# PCB_3U_DDS.net
KiCad netlist of a schematic drawn in Altium Designer
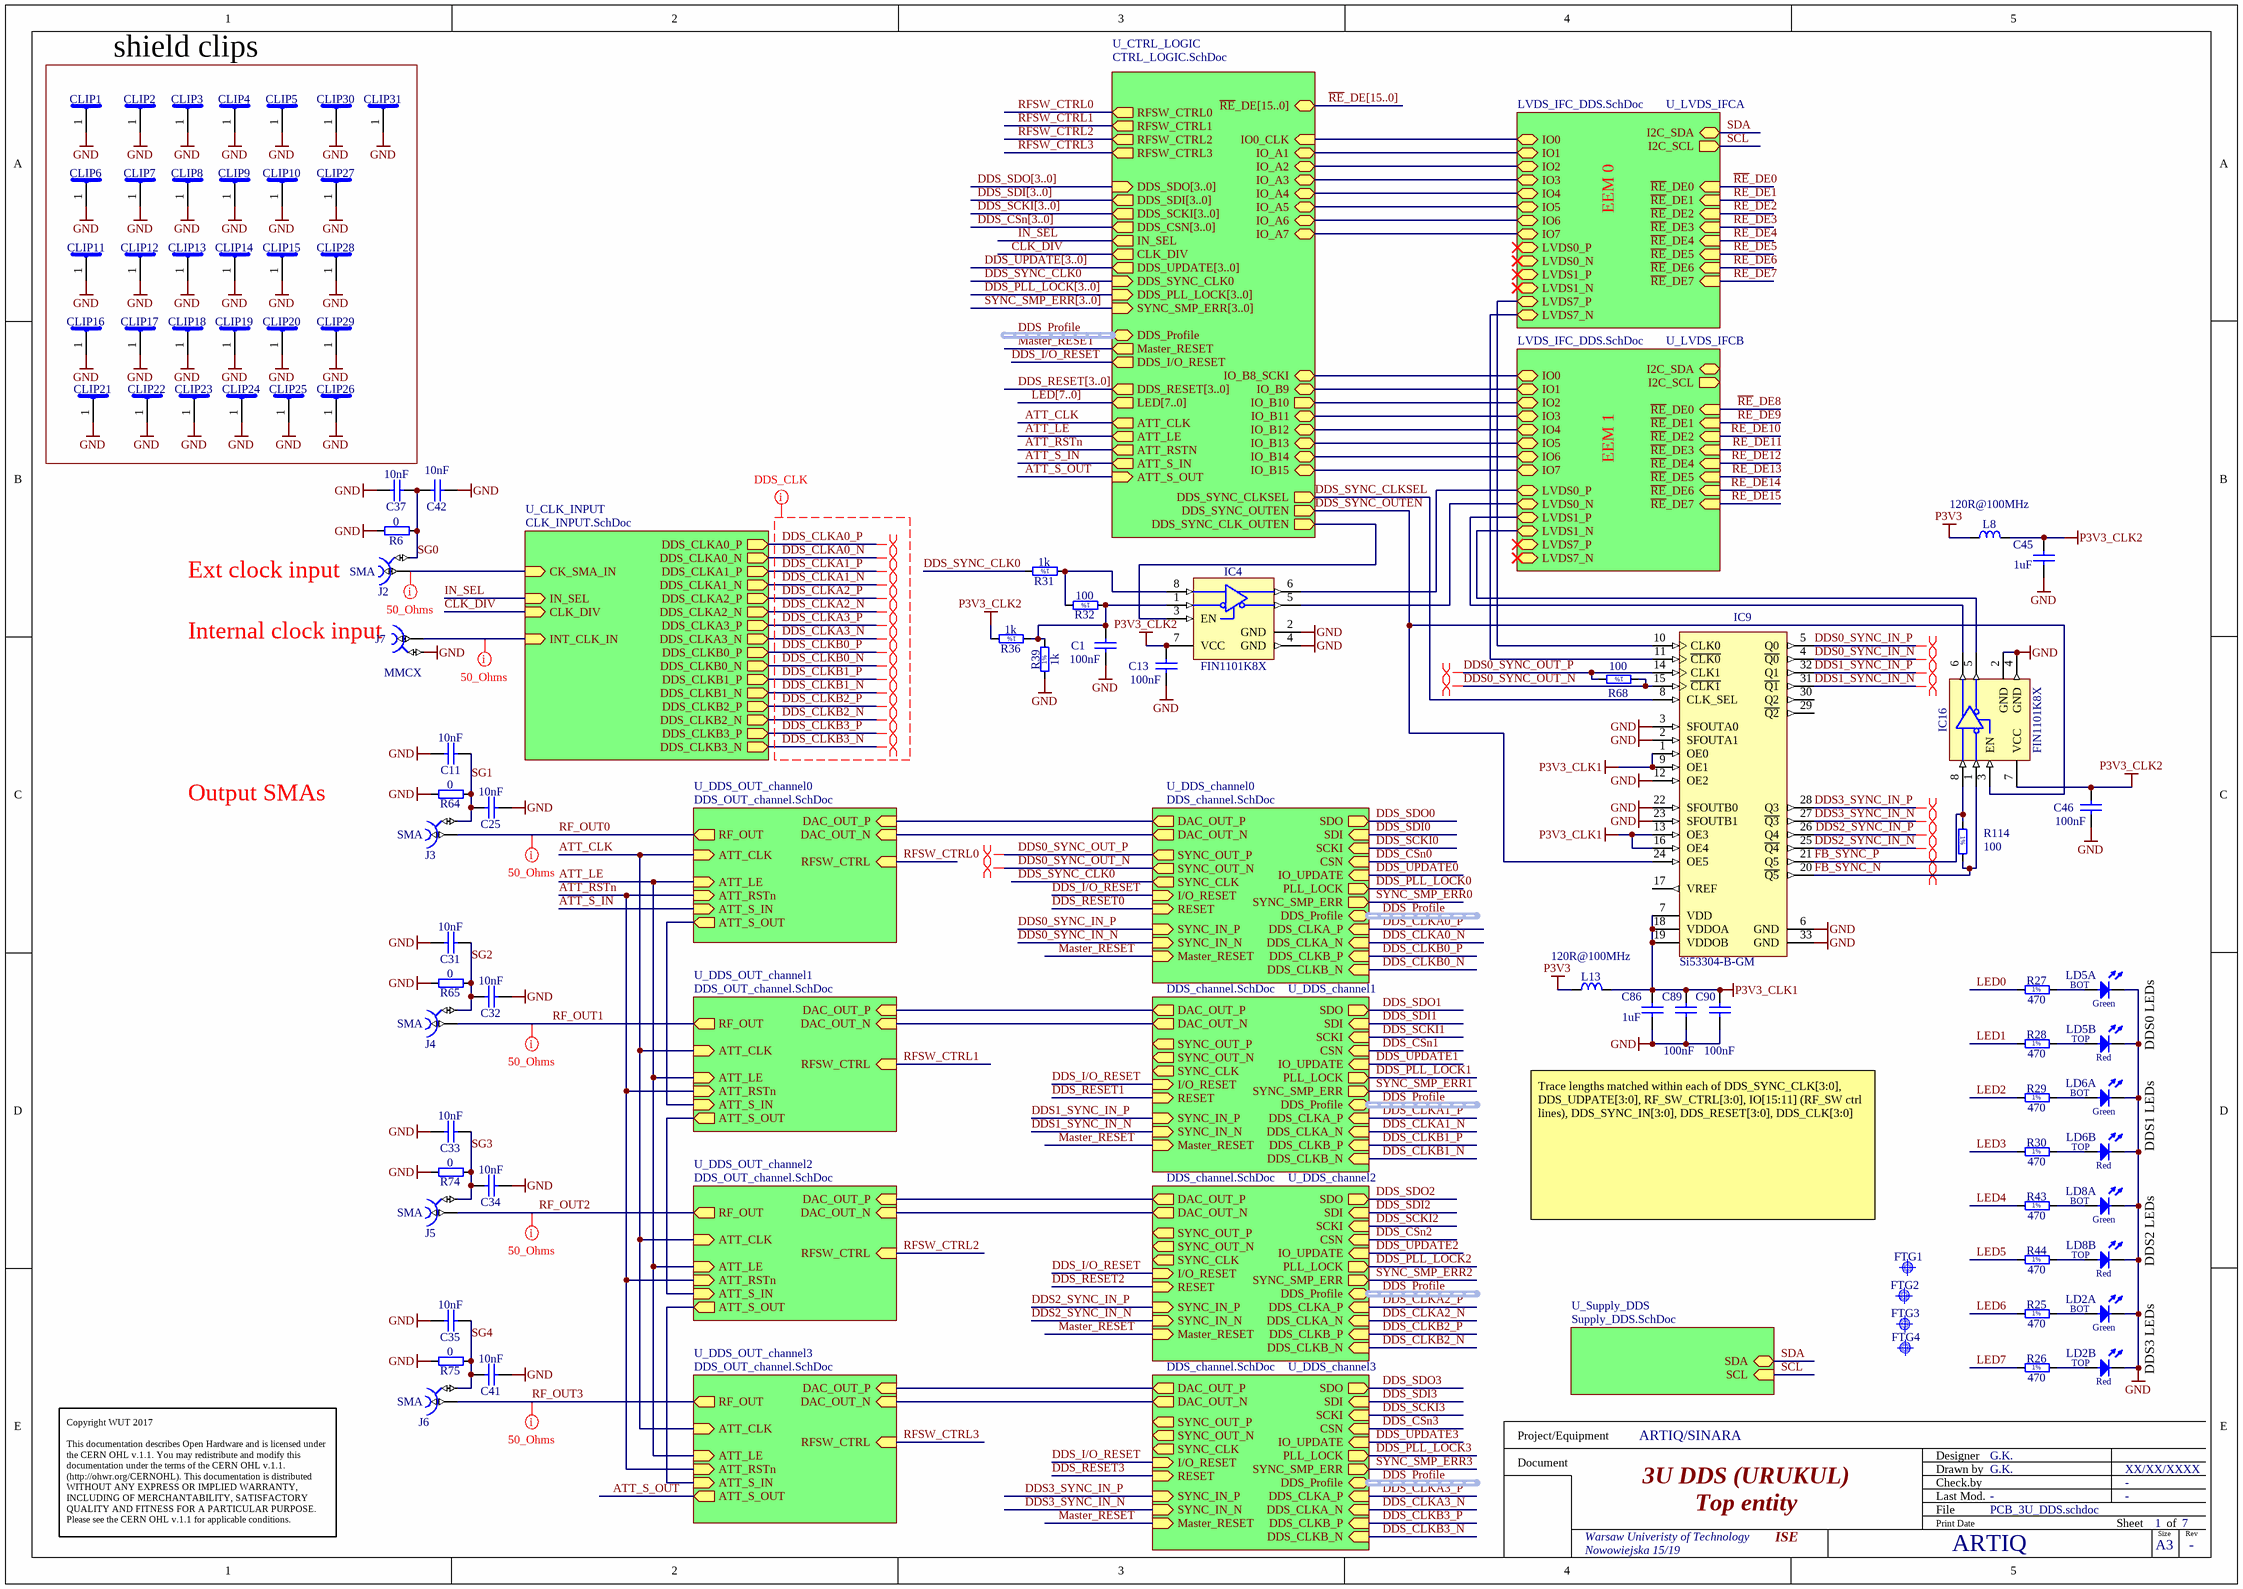
[diagram p0: PCB_3U_DDS.schdoc]

(export (version "E")
  (design (tool "Eeschema 10.0.6"))
  (components
    (comp (ref "C1")
      (value "100nF")
      (footprint "CAPC1005X55N")
      (description "Non-polarised capacitor")
      (fields
        (field (name "PART NUMBER") "CC0402_100NF_16V_10%_X5R")
        (field (name "VOLTAGE") "16V")
        (field (name "AUTHOR") "CERN DEM JLC")
      )
      (libsource (lib "Capacitors") (part "Capacitor - non polarized"))
    )
    (comp (ref "C11")
      (value "10nF")
      (footprint "CAPC1005X55N")
      (description "Non-polarised capacitor")
      (fields
        (field (name "PART NUMBER") "CC0402_10NF_16V_10%_X7R")
        (field (name "VOLTAGE") "16V")
        (field (name "AUTHOR") "CERN DEM JLC")
      )
      (libsource (lib "Capacitors") (part "Capacitor - non polarized"))
    )
    (comp (ref "C13")
      (value "100nF")
      (footprint "CAPC1005X55N")
      (description "Non-polarised capacitor")
      (fields
        (field (name "PART NUMBER") "CC0402_100NF_16V_10%_X5R")
        (field (name "VOLTAGE") "16V")
        (field (name "AUTHOR") "CERN DEM JLC")
      )
      (libsource (lib "Capacitors") (part "Capacitor - non polarized"))
    )
    (comp (ref "C25")
      (value "10nF")
      (footprint "CAPC1005X55N")
      (description "Non-polarised capacitor")
      (fields
        (field (name "PART NUMBER") "CC0402_10NF_16V_10%_X7R")
        (field (name "VOLTAGE") "16V")
        (field (name "AUTHOR") "CERN DEM JLC")
      )
      (libsource (lib "Capacitors") (part "Capacitor - non polarized"))
    )
    (comp (ref "C31")
      (value "10nF")
      (footprint "CAPC1005X55N")
      (description "Non-polarised capacitor")
      (fields
        (field (name "PART NUMBER") "CC0402_10NF_16V_10%_X7R")
        (field (name "VOLTAGE") "16V")
        (field (name "AUTHOR") "CERN DEM JLC")
      )
      (libsource (lib "Capacitors") (part "Capacitor - non polarized"))
    )
    (comp (ref "C32")
      (value "10nF")
      (footprint "CAPC1005X55N")
      (description "Non-polarised capacitor")
      (fields
        (field (name "PART NUMBER") "CC0402_10NF_16V_10%_X7R")
        (field (name "VOLTAGE") "16V")
        (field (name "AUTHOR") "CERN DEM JLC")
      )
      (libsource (lib "Capacitors") (part "Capacitor - non polarized"))
    )
    (comp (ref "C33")
      (value "10nF")
      (footprint "CAPC1005X55N")
      (description "Non-polarised capacitor")
      (fields
        (field (name "PART NUMBER") "CC0402_10NF_16V_10%_X7R")
        (field (name "VOLTAGE") "16V")
        (field (name "AUTHOR") "CERN DEM JLC")
      )
      (libsource (lib "Capacitors") (part "Capacitor - non polarized"))
    )
    (comp (ref "C34")
      (value "10nF")
      (footprint "CAPC1005X55N")
      (description "Non-polarised capacitor")
      (fields
        (field (name "PART NUMBER") "CC0402_10NF_16V_10%_X7R")
        (field (name "VOLTAGE") "16V")
        (field (name "AUTHOR") "CERN DEM JLC")
      )
      (libsource (lib "Capacitors") (part "Capacitor - non polarized"))
    )
    (comp (ref "C35")
      (value "10nF")
      (footprint "CAPC1005X55N")
      (description "Non-polarised capacitor")
      (fields
        (field (name "PART NUMBER") "CC0402_10NF_16V_10%_X7R")
        (field (name "VOLTAGE") "16V")
        (field (name "AUTHOR") "CERN DEM JLC")
      )
      (libsource (lib "Capacitors") (part "Capacitor - non polarized"))
    )
    (comp (ref "C37")
      (value "10nF")
      (footprint "CAPC1005X55N")
      (description "Non-polarised capacitor")
      (fields
        (field (name "PART NUMBER") "CC0402_10NF_16V_10%_X7R")
        (field (name "VOLTAGE") "16V")
        (field (name "AUTHOR") "CERN DEM JLC")
      )
      (libsource (lib "Capacitors") (part "Capacitor - non polarized"))
    )
    (comp (ref "C41")
      (value "10nF")
      (footprint "CAPC1005X55N")
      (description "Non-polarised capacitor")
      (fields
        (field (name "PART NUMBER") "CC0402_10NF_16V_10%_X7R")
        (field (name "VOLTAGE") "16V")
        (field (name "AUTHOR") "CERN DEM JLC")
      )
      (libsource (lib "Capacitors") (part "Capacitor - non polarized"))
    )
    (comp (ref "C42")
      (value "10nF")
      (footprint "CAPC1005X55N")
      (description "Non-polarised capacitor")
      (fields
        (field (name "PART NUMBER") "CC0402_10NF_16V_10%_X7R")
        (field (name "VOLTAGE") "16V")
        (field (name "AUTHOR") "CERN DEM JLC")
      )
      (libsource (lib "Capacitors") (part "Capacitor - non polarized"))
    )
    (comp (ref "C45")
      (value "1uF")
      (footprint "CAPC1005X55N")
      (description "Non-polarised capacitor")
      (fields
        (field (name "PART NUMBER") "CC0402_1UF_16V_10%_X5R")
        (field (name "VOLTAGE") "16V")
        (field (name "AUTHOR") "CERN DEM JLC")
      )
      (libsource (lib "Capacitors") (part "Capacitor - non polarized"))
    )
    (comp (ref "C46")
      (value "100nF")
      (footprint "CAPC1005X55N")
      (description "Non-polarised capacitor")
      (fields
        (field (name "PART NUMBER") "CC0402_100NF_16V_10%_X5R")
        (field (name "VOLTAGE") "16V")
        (field (name "AUTHOR") "CERN DEM JLC")
      )
      (libsource (lib "Capacitors") (part "Capacitor - non polarized"))
    )
    (comp (ref "C86")
      (value "1uF")
      (footprint "CAPC1005X55N")
      (description "Non-polarised capacitor")
      (fields
        (field (name "PART NUMBER") "CC0402_1UF_16V_10%_X5R")
        (field (name "VOLTAGE") "16V")
        (field (name "AUTHOR") "CERN DEM JLC")
      )
      (libsource (lib "Capacitors") (part "Capacitor - non polarized"))
    )
    (comp (ref "C89")
      (value "100nF")
      (footprint "CAPC1005X55N")
      (description "Non-polarised capacitor")
      (fields
        (field (name "PART NUMBER") "CC0402_100NF_16V_10%_X5R")
        (field (name "VOLTAGE") "16V")
        (field (name "AUTHOR") "CERN DEM JLC")
      )
      (libsource (lib "Capacitors") (part "Capacitor - non polarized"))
    )
    (comp (ref "C90")
      (value "100nF")
      (footprint "CAPC1005X55N")
      (description "Non-polarised capacitor")
      (fields
        (field (name "PART NUMBER") "CC0402_100NF_16V_10%_X5R")
        (field (name "VOLTAGE") "16V")
        (field (name "AUTHOR") "CERN DEM JLC")
      )
      (libsource (lib "Capacitors") (part "Capacitor - non polarized"))
    )
    (comp (ref "CLIP1")
      (value "S1411-46R")
      (footprint "CLIP_HOLLAND-SHIELDING_LC")
      (description "Surface Mount Clip for PCB Screening Covers")
      (fields (field (name "MANUFACTURER") "HARWIN") (field (name "AUTHOR") "CERN DEM JLC"))
      (libsource (lib "LIBRARY_SCH") (part "SHIELD_CLIP"))
    )
    (comp (ref "CLIP2")
      (value "S1411-46R")
      (footprint "CLIP_HOLLAND-SHIELDING_LC")
      (description "Surface Mount Clip for PCB Screening Covers")
      (fields (field (name "MANUFACTURER") "HARWIN") (field (name "AUTHOR") "CERN DEM JLC"))
      (libsource (lib "LIBRARY_SCH") (part "SHIELD_CLIP"))
    )
    (comp (ref "CLIP3")
      (value "S1411-46R")
      (footprint "CLIP_HOLLAND-SHIELDING_LC")
      (description "Surface Mount Clip for PCB Screening Covers")
      (fields (field (name "MANUFACTURER") "HARWIN") (field (name "AUTHOR") "CERN DEM JLC"))
      (libsource (lib "LIBRARY_SCH") (part "SHIELD_CLIP"))
    )
    (comp (ref "CLIP4")
      (value "S1411-46R")
      (footprint "CLIP_HOLLAND-SHIELDING_LC")
      (description "Surface Mount Clip for PCB Screening Covers")
      (fields (field (name "MANUFACTURER") "HARWIN") (field (name "AUTHOR") "CERN DEM JLC"))
      (libsource (lib "LIBRARY_SCH") (part "SHIELD_CLIP"))
    )
    (comp (ref "CLIP5")
      (value "S1411-46R")
      (footprint "CLIP_HOLLAND-SHIELDING_LC")
      (description "Surface Mount Clip for PCB Screening Covers")
      (fields (field (name "MANUFACTURER") "HARWIN") (field (name "AUTHOR") "CERN DEM JLC"))
      (libsource (lib "LIBRARY_SCH") (part "SHIELD_CLIP"))
    )
    (comp (ref "CLIP6")
      (value "S1411-46R")
      (footprint "CLIP_HOLLAND-SHIELDING_LC")
      (description "Surface Mount Clip for PCB Screening Covers")
      (fields (field (name "MANUFACTURER") "HARWIN") (field (name "AUTHOR") "CERN DEM JLC"))
      (libsource (lib "LIBRARY_SCH") (part "SHIELD_CLIP"))
    )
    (comp (ref "CLIP7")
      (value "S1411-46R")
      (footprint "CLIP_HOLLAND-SHIELDING_LC")
      (description "Surface Mount Clip for PCB Screening Covers")
      (fields (field (name "MANUFACTURER") "HARWIN") (field (name "AUTHOR") "CERN DEM JLC"))
      (libsource (lib "LIBRARY_SCH") (part "SHIELD_CLIP"))
    )
    (comp (ref "CLIP8")
      (value "S1411-46R")
      (footprint "CLIP_HOLLAND-SHIELDING_LC")
      (description "Surface Mount Clip for PCB Screening Covers")
      (fields (field (name "MANUFACTURER") "HARWIN") (field (name "AUTHOR") "CERN DEM JLC"))
      (libsource (lib "LIBRARY_SCH") (part "SHIELD_CLIP"))
    )
    (comp (ref "CLIP9")
      (value "S1411-46R")
      (footprint "CLIP_HOLLAND-SHIELDING_LC")
      (description "Surface Mount Clip for PCB Screening Covers")
      (fields (field (name "MANUFACTURER") "HARWIN") (field (name "AUTHOR") "CERN DEM JLC"))
      (libsource (lib "LIBRARY_SCH") (part "SHIELD_CLIP"))
    )
    (comp (ref "CLIP10")
      (value "S1411-46R")
      (footprint "CLIP_HOLLAND-SHIELDING_LC")
      (description "Surface Mount Clip for PCB Screening Covers")
      (fields (field (name "MANUFACTURER") "HARWIN") (field (name "AUTHOR") "CERN DEM JLC"))
      (libsource (lib "LIBRARY_SCH") (part "SHIELD_CLIP"))
    )
    (comp (ref "CLIP11")
      (value "S1411-46R")
      (footprint "CLIP_HOLLAND-SHIELDING_LC")
      (description "Surface Mount Clip for PCB Screening Covers")
      (fields (field (name "MANUFACTURER") "HARWIN") (field (name "AUTHOR") "CERN DEM JLC"))
      (libsource (lib "LIBRARY_SCH") (part "SHIELD_CLIP"))
    )
    (comp (ref "CLIP12")
      (value "S1411-46R")
      (footprint "CLIP_HOLLAND-SHIELDING_LC")
      (description "Surface Mount Clip for PCB Screening Covers")
      (fields (field (name "MANUFACTURER") "HARWIN") (field (name "AUTHOR") "CERN DEM JLC"))
      (libsource (lib "LIBRARY_SCH") (part "SHIELD_CLIP"))
    )
    (comp (ref "CLIP13")
      (value "S1411-46R")
      (footprint "CLIP_HOLLAND-SHIELDING_LC")
      (description "Surface Mount Clip for PCB Screening Covers")
      (fields (field (name "MANUFACTURER") "HARWIN") (field (name "AUTHOR") "CERN DEM JLC"))
      (libsource (lib "LIBRARY_SCH") (part "SHIELD_CLIP"))
    )
    (comp (ref "CLIP14")
      (value "S1411-46R")
      (footprint "CLIP_HOLLAND-SHIELDING_LC")
      (description "Surface Mount Clip for PCB Screening Covers")
      (fields (field (name "MANUFACTURER") "HARWIN") (field (name "AUTHOR") "CERN DEM JLC"))
      (libsource (lib "LIBRARY_SCH") (part "SHIELD_CLIP"))
    )
    (comp (ref "CLIP15")
      (value "S1411-46R")
      (footprint "CLIP_HOLLAND-SHIELDING_LC")
      (description "Surface Mount Clip for PCB Screening Covers")
      (fields (field (name "MANUFACTURER") "HARWIN") (field (name "AUTHOR") "CERN DEM JLC"))
      (libsource (lib "LIBRARY_SCH") (part "SHIELD_CLIP"))
    )
    (comp (ref "CLIP16")
      (value "S1411-46R")
      (footprint "CLIP_HOLLAND-SHIELDING_LC")
      (description "Surface Mount Clip for PCB Screening Covers")
      (fields (field (name "MANUFACTURER") "HARWIN") (field (name "AUTHOR") "CERN DEM JLC"))
      (libsource (lib "LIBRARY_SCH") (part "SHIELD_CLIP"))
    )
    (comp (ref "CLIP17")
      (value "S1411-46R")
      (footprint "CLIP_HOLLAND-SHIELDING_LC")
      (description "Surface Mount Clip for PCB Screening Covers")
      (fields (field (name "MANUFACTURER") "HARWIN") (field (name "AUTHOR") "CERN DEM JLC"))
      (libsource (lib "LIBRARY_SCH") (part "SHIELD_CLIP"))
    )
    (comp (ref "CLIP18")
      (value "S1411-46R")
      (footprint "CLIP_HOLLAND-SHIELDING_LC")
      (description "Surface Mount Clip for PCB Screening Covers")
      (fields (field (name "MANUFACTURER") "HARWIN") (field (name "AUTHOR") "CERN DEM JLC"))
      (libsource (lib "LIBRARY_SCH") (part "SHIELD_CLIP"))
    )
    (comp (ref "CLIP19")
      (value "S1411-46R")
      (footprint "CLIP_HOLLAND-SHIELDING_LC")
      (description "Surface Mount Clip for PCB Screening Covers")
      (fields (field (name "MANUFACTURER") "HARWIN") (field (name "AUTHOR") "CERN DEM JLC"))
      (libsource (lib "LIBRARY_SCH") (part "SHIELD_CLIP"))
    )
    (comp (ref "CLIP20")
      (value "S1411-46R")
      (footprint "CLIP_HOLLAND-SHIELDING_LC")
      (description "Surface Mount Clip for PCB Screening Covers")
      (fields (field (name "MANUFACTURER") "HARWIN") (field (name "AUTHOR") "CERN DEM JLC"))
      (libsource (lib "LIBRARY_SCH") (part "SHIELD_CLIP"))
    )
    (comp (ref "CLIP21")
      (value "S1411-46R")
      (footprint "CLIP_HOLLAND-SHIELDING_LC")
      (description "Surface Mount Clip for PCB Screening Covers")
      (fields (field (name "MANUFACTURER") "HARWIN") (field (name "AUTHOR") "CERN DEM JLC"))
      (libsource (lib "LIBRARY_SCH") (part "SHIELD_CLIP"))
    )
    (comp (ref "CLIP22")
      (value "S1411-46R")
      (footprint "CLIP_HOLLAND-SHIELDING_LC")
      (description "Surface Mount Clip for PCB Screening Covers")
      (fields (field (name "MANUFACTURER") "HARWIN") (field (name "AUTHOR") "CERN DEM JLC"))
      (libsource (lib "LIBRARY_SCH") (part "SHIELD_CLIP"))
    )
    (comp (ref "CLIP23")
      (value "S1411-46R")
      (footprint "CLIP_HOLLAND-SHIELDING_LC")
      (description "Surface Mount Clip for PCB Screening Covers")
      (fields (field (name "MANUFACTURER") "HARWIN") (field (name "AUTHOR") "CERN DEM JLC"))
      (libsource (lib "LIBRARY_SCH") (part "SHIELD_CLIP"))
    )
    (comp (ref "CLIP24")
      (value "S1411-46R")
      (footprint "CLIP_HOLLAND-SHIELDING_LC")
      (description "Surface Mount Clip for PCB Screening Covers")
      (fields (field (name "MANUFACTURER") "HARWIN") (field (name "AUTHOR") "CERN DEM JLC"))
      (libsource (lib "LIBRARY_SCH") (part "SHIELD_CLIP"))
    )
    (comp (ref "CLIP25")
      (value "S1411-46R")
      (footprint "CLIP_HOLLAND-SHIELDING_LC")
      (description "Surface Mount Clip for PCB Screening Covers")
      (fields (field (name "MANUFACTURER") "HARWIN") (field (name "AUTHOR") "CERN DEM JLC"))
      (libsource (lib "LIBRARY_SCH") (part "SHIELD_CLIP"))
    )
    (comp (ref "CLIP26")
      (value "S1411-46R")
      (footprint "CLIP_HOLLAND-SHIELDING_LC")
      (description "Surface Mount Clip for PCB Screening Covers")
      (fields (field (name "MANUFACTURER") "HARWIN") (field (name "AUTHOR") "CERN DEM JLC"))
      (libsource (lib "LIBRARY_SCH") (part "SHIELD_CLIP"))
    )
    (comp (ref "CLIP27")
      (value "S1411-46R")
      (footprint "CLIP_HOLLAND-SHIELDING_LC")
      (description "Surface Mount Clip for PCB Screening Covers")
      (fields (field (name "MANUFACTURER") "HARWIN") (field (name "AUTHOR") "CERN DEM JLC"))
      (libsource (lib "LIBRARY_SCH") (part "SHIELD_CLIP"))
    )
    (comp (ref "CLIP28")
      (value "S1411-46R")
      (footprint "CLIP_HOLLAND-SHIELDING_LC")
      (description "Surface Mount Clip for PCB Screening Covers")
      (fields (field (name "MANUFACTURER") "HARWIN") (field (name "AUTHOR") "CERN DEM JLC"))
      (libsource (lib "LIBRARY_SCH") (part "SHIELD_CLIP"))
    )
    (comp (ref "CLIP29")
      (value "S1411-46R")
      (footprint "CLIP_HOLLAND-SHIELDING_LC")
      (description "Surface Mount Clip for PCB Screening Covers")
      (fields (field (name "MANUFACTURER") "HARWIN") (field (name "AUTHOR") "CERN DEM JLC"))
      (libsource (lib "LIBRARY_SCH") (part "SHIELD_CLIP"))
    )
    (comp (ref "CLIP30")
      (value "S1411-46R")
      (footprint "CLIP_HOLLAND-SHIELDING_LC")
      (description "Surface Mount Clip for PCB Screening Covers")
      (fields (field (name "MANUFACTURER") "HARWIN") (field (name "AUTHOR") "CERN DEM JLC"))
      (libsource (lib "LIBRARY_SCH") (part "SHIELD_CLIP"))
    )
    (comp (ref "CLIP31")
      (value "S1411-46R")
      (footprint "CLIP_HOLLAND-SHIELDING_LC")
      (description "Surface Mount Clip for PCB Screening Covers")
      (fields (field (name "MANUFACTURER") "HARWIN") (field (name "AUTHOR") "CERN DEM JLC"))
      (libsource (lib "LIBRARY_SCH") (part "SHIELD_CLIP"))
    )
    (comp (ref "FTG1")
      (value "Use only in PCB")
      (footprint "FIDUCIAL_TOP_C100-200")
      (description "Fiducial Target")
      (fields (field (name "PART NUMBER") "FIDUCIAL_TARGET_C100-200") (field (name "AUTHOR") "CERN DEM JLC"))
      (libsource (lib "Eletro-mechanical") (part "Fiducial Target"))
    )
    (comp (ref "FTG2")
      (value "Use only in PCB")
      (footprint "FIDUCIAL_TOP_S100-200")
      (description "Fiducial Target")
      (fields (field (name "PART NUMBER") "FIDUCIAL_TARGET_S100-200") (field (name "AUTHOR") "CERN DEM JLC"))
      (libsource (lib "Eletro-mechanical") (part "Fiducial Target"))
    )
    (comp (ref "FTG3")
      (value "Use only in PCB")
      (footprint "FIDUCIAL_TOP_S200-400")
      (description "Fiducial Target")
      (fields (field (name "PART NUMBER") "FIDUCIAL_TARGET_S200-400") (field (name "AUTHOR") "CERN DEM JLC"))
      (libsource (lib "Eletro-mechanical") (part "Fiducial Target"))
    )
    (comp (ref "FTG4")
      (value "Use only in PCB")
      (footprint "FIDUCIAL_TOP_S100-200")
      (description "Fiducial Target")
      (fields (field (name "PART NUMBER") "FIDUCIAL_TARGET_S100-200") (field (name "AUTHOR") "CERN DEM JLC"))
      (libsource (lib "Eletro-mechanical") (part "Fiducial Target"))
    )
    (comp (ref "IC4")
      (value "FIN1101K8X")
      (footprint "SOP50P310X90-8N")
      (description "LVDS Single Port High Speed Repeater")
      (fields (field (name "MANUFACTURER") "FAIRCHILD SEMICONDUCTOR") (field (name "AUTHOR") "CERN DEM JLC"))
      (libsource (lib "") (part "FIN1101K8X_1"))
    )
    (comp (ref "IC9")
      (value "Si53304-B-GM")
      (footprint "SLAB-QFN-32-2150x2150TP_M")
      (fields (field (name "MANUFACTURER") "Silicon Labs"))
      (libsource (lib "Altium Content Vault") (part "SLAB-Si533X4-QFN-32-33"))
    )
    (comp (ref "IC16")
      (value "FIN1101K8X")
      (footprint "SOP50P310X90-8N")
      (description "LVDS Single Port High Speed Repeater")
      (fields (field (name "MANUFACTURER") "FAIRCHILD SEMICONDUCTOR") (field (name "AUTHOR") "CERN DEM JLC"))
      (libsource (lib "ICs And Semiconductors") (part "FIN1101K8X"))
    )
    (comp (ref "J2")
      (value "SMA")
      (footprint "RF249BT0050GHDW")
      (description "50 Ohm Through Hole SMA Right Angle PCB Jack")
      (fields
        (field (name "PART NUMBER") "AdamTech_RF249BT0050GHDW")
        (field (name "MANUFACTURER") "AdamTech")
        (field (name "AUTHOR") "GK")
      )
      (libsource (lib "LIBRARY_SCH") (part "CON_SMA_RF249BT0050GHDW"))
    )
    (comp (ref "J3")
      (value "SMA")
      (footprint "RF249BT0050GHDW")
      (description "50 Ohm Through Hole SMA Right Angle PCB Jack")
      (fields
        (field (name "PART NUMBER") "AdamTech_RF249BT0050GHDW")
        (field (name "MANUFACTURER") "AdamTech")
        (field (name "AUTHOR") "GK")
      )
      (libsource (lib "LIBRARY_SCH") (part "CON_SMA_RF249BT0050GHDW"))
    )
    (comp (ref "J4")
      (value "SMA")
      (footprint "RF249BT0050GHDW")
      (description "50 Ohm Through Hole SMA Right Angle PCB Jack")
      (fields
        (field (name "PART NUMBER") "AdamTech_RF249BT0050GHDW")
        (field (name "MANUFACTURER") "AdamTech")
        (field (name "AUTHOR") "GK")
      )
      (libsource (lib "LIBRARY_SCH") (part "CON_SMA_RF249BT0050GHDW"))
    )
    (comp (ref "J5")
      (value "SMA")
      (footprint "RF249BT0050GHDW")
      (description "50 Ohm Through Hole SMA Right Angle PCB Jack")
      (fields
        (field (name "PART NUMBER") "AdamTech_RF249BT0050GHDW")
        (field (name "MANUFACTURER") "AdamTech")
        (field (name "AUTHOR") "GK")
      )
      (libsource (lib "LIBRARY_SCH") (part "CON_SMA_RF249BT0050GHDW"))
    )
    (comp (ref "J6")
      (value "SMA")
      (footprint "RF249BT0050GHDW")
      (description "50 Ohm Through Hole SMA Right Angle PCB Jack")
      (fields
        (field (name "PART NUMBER") "AdamTech_RF249BT0050GHDW")
        (field (name "MANUFACTURER") "AdamTech")
        (field (name "AUTHOR") "GK")
      )
      (libsource (lib "LIBRARY_SCH") (part "CON_SMA_RF249BT0050GHDW"))
    )
    (comp (ref "J7")
      (value "MMCX")
      (footprint "SAMTEC_MMCX-J-P-H-ST-TH1")
      (fields
        (field (name "PART NUMBER") "SAMTEC_MMCX-J-P-H-ST-TH1")
        (field (name "MANUFACTURER") "SAMTEC")
        (field (name "MANUFACTURER PART NUMBER") "MMCX-J-P-H-ST-TH1")
        (field (name "AUTHOR") "CERN DEM JLC")
      )
      (libsource (lib "Connectors") (part "Coax_1Female_1Shield"))
    )
    (comp (ref "L8")
      (value "120R@100MHz")
      (footprint "INDC1608X95N")
      (description "Inductor")
      (fields
        (field (name "PART NUMBER") "IND0603_MURATA_BLM18PG121SN1D")
        (field (name "POWER") "2A")
        (field (name "AUTHOR") "CERN DEM BC")
      )
      (libsource (lib "Inductors & Transformers") (part "Inductor"))
    )
    (comp (ref "L13")
      (value "120R@100MHz")
      (footprint "INDC1608X95N")
      (description "Inductor")
      (fields
        (field (name "PART NUMBER") "IND0603_MURATA_BLM18PG121SN1D")
        (field (name "POWER") "2A")
        (field (name "AUTHOR") "CERN DEM BC")
      )
      (libsource (lib "Inductors & Transformers") (part "Inductor"))
    )
    (comp (ref "LD2")
      (value "Red/Green")
      (footprint "LED_DIALIGHT_553-0112-200F")
      (description "2x LED  Botom Green, Top Red")
      (fields
        (field (name "PART NUMBER") "LED_DIALIGHT_553-0112-200F")
        (field (name "MANUFACTURER") "DIALIGHT")
        (field (name "AUTHOR") "CERN DEM JMW")
      )
      (libsource (lib "ICs And Semiconductors") (part "LED x2 G-1C2A-BOT_R-3C4A-TOP"))
    )
    (comp (ref "LD5")
      (value "Red/Green")
      (footprint "LED_DIALIGHT_553-0112-200F")
      (description "2x LED  Botom Green, Top Red")
      (fields
        (field (name "PART NUMBER") "LED_DIALIGHT_553-0112-200F")
        (field (name "MANUFACTURER") "DIALIGHT")
        (field (name "AUTHOR") "CERN DEM JMW")
      )
      (libsource (lib "ICs And Semiconductors") (part "LED x2 G-1C2A-BOT_R-3C4A-TOP"))
    )
    (comp (ref "LD6")
      (value "Red/Green")
      (footprint "LED_DIALIGHT_553-0112-200F")
      (description "2x LED  Botom Green, Top Red")
      (fields
        (field (name "PART NUMBER") "LED_DIALIGHT_553-0112-200F")
        (field (name "MANUFACTURER") "DIALIGHT")
        (field (name "AUTHOR") "CERN DEM JMW")
      )
      (libsource (lib "ICs And Semiconductors") (part "LED x2 G-1C2A-BOT_R-3C4A-TOP"))
    )
    (comp (ref "LD8")
      (value "Red/Green")
      (footprint "LED_DIALIGHT_553-0112-200F")
      (description "2x LED  Botom Green, Top Red")
      (fields
        (field (name "PART NUMBER") "LED_DIALIGHT_553-0112-200F")
        (field (name "MANUFACTURER") "DIALIGHT")
        (field (name "AUTHOR") "CERN DEM JMW")
      )
      (libsource (lib "ICs And Semiconductors") (part "LED x2 G-1C2A-BOT_R-3C4A-TOP"))
    )
    (comp (ref "R6")
      (value "0")
      (footprint "RESC1005X40N")
      (description "Resistor")
      (fields
        (field (name "PART NUMBER") "R0402_0R_JUMPER")
        (field (name "MANUFACTURER") "GENERIC")
        (field (name "AUTHOR") "CERN DEM JLC")
      )
      (libsource (lib "Resistors") (part "Resistor"))
    )
    (comp (ref "R25")
      (value "470")
      (footprint "RESC1005X40N")
      (description "Resistor - 1%")
      (fields
        (field (name "PART NUMBER") "R0402_470R_1%_0.0625W_100PPM")
        (field (name "POWER") "0.0625W")
        (field (name "AUTHOR") "CERN DEM JLC")
      )
      (libsource (lib "Resistors") (part "Resistor - 1%"))
    )
    (comp (ref "R26")
      (value "470")
      (footprint "RESC1005X40N")
      (description "Resistor - 1%")
      (fields
        (field (name "PART NUMBER") "R0402_470R_1%_0.0625W_100PPM")
        (field (name "POWER") "0.0625W")
        (field (name "AUTHOR") "CERN DEM JLC")
      )
      (libsource (lib "Resistors") (part "Resistor - 1%"))
    )
    (comp (ref "R27")
      (value "470")
      (footprint "RESC1005X40N")
      (description "Resistor - 1%")
      (fields
        (field (name "PART NUMBER") "R0402_470R_1%_0.0625W_100PPM")
        (field (name "POWER") "0.0625W")
        (field (name "AUTHOR") "CERN DEM JLC")
      )
      (libsource (lib "Resistors") (part "Resistor - 1%"))
    )
    (comp (ref "R28")
      (value "470")
      (footprint "RESC1005X40N")
      (description "Resistor - 1%")
      (fields
        (field (name "PART NUMBER") "R0402_470R_1%_0.0625W_100PPM")
        (field (name "POWER") "0.0625W")
        (field (name "AUTHOR") "CERN DEM JLC")
      )
      (libsource (lib "Resistors") (part "Resistor - 1%"))
    )
    (comp (ref "R29")
      (value "470")
      (footprint "RESC1005X40N")
      (description "Resistor - 1%")
      (fields
        (field (name "PART NUMBER") "R0402_470R_1%_0.0625W_100PPM")
        (field (name "POWER") "0.0625W")
        (field (name "AUTHOR") "CERN DEM JLC")
      )
      (libsource (lib "Resistors") (part "Resistor - 1%"))
    )
    (comp (ref "R30")
      (value "470")
      (footprint "RESC1005X40N")
      (description "Resistor - 1%")
      (fields
        (field (name "PART NUMBER") "R0402_470R_1%_0.0625W_100PPM")
        (field (name "POWER") "0.0625W")
        (field (name "AUTHOR") "CERN DEM JLC")
      )
      (libsource (lib "Resistors") (part "Resistor - 1%"))
    )
    (comp (ref "R31")
      (value "1k")
      (footprint "RESC1005X40N")
      (description "Resistor - 1%")
      (fields
        (field (name "PART NUMBER") "R0402_1K_1%_0.0625W_100PPM")
        (field (name "POWER") "0.0625W")
        (field (name "AUTHOR") "CERN DEM JLC")
      )
      (libsource (lib "Resistors") (part "Resistor - 1%"))
    )
    (comp (ref "R32")
      (value "100")
      (footprint "RESC1005X40N")
      (description "Resistor - 1%")
      (fields
        (field (name "PART NUMBER") "R0402_100R_1%_0.0625W_100PPM")
        (field (name "POWER") "0.0625W")
        (field (name "AUTHOR") "CERN DEM JLC")
      )
      (libsource (lib "Resistors") (part "Resistor - 1%"))
    )
    (comp (ref "R36")
      (value "1k")
      (footprint "RESC1005X40N")
      (description "Resistor - 1%")
      (fields
        (field (name "PART NUMBER") "R0402_1K_1%_0.0625W_100PPM")
        (field (name "POWER") "0.0625W")
        (field (name "AUTHOR") "CERN DEM JLC")
      )
      (libsource (lib "Resistors") (part "Resistor - 1%"))
    )
    (comp (ref "R39")
      (value "1k")
      (footprint "RESC1005X40N")
      (description "Resistor - 1%")
      (fields
        (field (name "PART NUMBER") "R0402_1K_1%_0.0625W_100PPM")
        (field (name "POWER") "0.0625W")
        (field (name "AUTHOR") "CERN DEM JLC")
      )
      (libsource (lib "Resistors") (part "Resistor - 1%"))
    )
    (comp (ref "R43")
      (value "470")
      (footprint "RESC1005X40N")
      (description "Resistor - 1%")
      (fields
        (field (name "PART NUMBER") "R0402_470R_1%_0.0625W_100PPM")
        (field (name "POWER") "0.0625W")
        (field (name "AUTHOR") "CERN DEM JLC")
      )
      (libsource (lib "Resistors") (part "Resistor - 1%"))
    )
    (comp (ref "R44")
      (value "470")
      (footprint "RESC1005X40N")
      (description "Resistor - 1%")
      (fields
        (field (name "PART NUMBER") "R0402_470R_1%_0.0625W_100PPM")
        (field (name "POWER") "0.0625W")
        (field (name "AUTHOR") "CERN DEM JLC")
      )
      (libsource (lib "Resistors") (part "Resistor - 1%"))
    )
    (comp (ref "R64")
      (value "0")
      (footprint "RESC1005X40N")
      (description "Resistor")
      (fields
        (field (name "PART NUMBER") "R0402_0R_JUMPER")
        (field (name "MANUFACTURER") "GENERIC")
        (field (name "AUTHOR") "CERN DEM JLC")
      )
      (libsource (lib "Resistors") (part "Resistor"))
    )
    (comp (ref "R65")
      (value "0")
      (footprint "RESC1005X40N")
      (description "Resistor")
      (fields
        (field (name "PART NUMBER") "R0402_0R_JUMPER")
        (field (name "MANUFACTURER") "GENERIC")
        (field (name "AUTHOR") "CERN DEM JLC")
      )
      (libsource (lib "Resistors") (part "Resistor"))
    )
    (comp (ref "R68")
      (value "100")
      (footprint "RESC1005X40N")
      (description "Resistor - 1%")
      (fields
        (field (name "PART NUMBER") "R0402_100R_1%_0.0625W_100PPM")
        (field (name "POWER") "0.0625W")
        (field (name "AUTHOR") "CERN DEM JLC")
      )
      (libsource (lib "Resistors") (part "Resistor - 1%"))
    )
    (comp (ref "R74")
      (value "0")
      (footprint "RESC1005X40N")
      (description "Resistor")
      (fields
        (field (name "PART NUMBER") "R0402_0R_JUMPER")
        (field (name "MANUFACTURER") "GENERIC")
        (field (name "AUTHOR") "CERN DEM JLC")
      )
      (libsource (lib "Resistors") (part "Resistor"))
    )
    (comp (ref "R75")
      (value "0")
      (footprint "RESC1005X40N")
      (description "Resistor")
      (fields
        (field (name "PART NUMBER") "R0402_0R_JUMPER")
        (field (name "MANUFACTURER") "GENERIC")
        (field (name "AUTHOR") "CERN DEM JLC")
      )
      (libsource (lib "Resistors") (part "Resistor"))
    )
    (comp (ref "R114")
      (value "100")
      (footprint "RESC1005X40N")
      (description "Resistor - 1%")
      (fields
        (field (name "PART NUMBER") "R0402_100R_1%_0.0625W_100PPM")
        (field (name "POWER") "0.0625W")
        (field (name "AUTHOR") "CERN DEM JLC")
      )
      (libsource (lib "Resistors") (part "Resistor - 1%"))
    )
  )
  (nets
    (net (code "10") (name "/CK_SMA_IN") (class "Default")
      (node (ref "J2") (pin "1") (pinfunction "1_1") (pintype "bidirectional"))
    )
    (net (code "20") (name "/DDS0_SYNC_IN_N") (class "Default")
      (node (ref "IC9") (pin "4") (pinfunction "~{Q0}_4") (pintype "output"))
    )
    (net (code "21") (name "/DDS0_SYNC_IN_P") (class "Default")
      (node (ref "IC9") (pin "5") (pinfunction "Q0_5") (pintype "output"))
    )
    (net (code "22") (name "/DDS0_SYNC_OUT_N") (class "Default")
      (node (ref "IC9") (pin "15") (pinfunction "~{CLK1}_15") (pintype "input"))
      (node (ref "R68") (pin "1") (pinfunction "1_1") (pintype "passive"))
    )
    (net (code "23") (name "/DDS0_SYNC_OUT_P") (class "Default")
      (node (ref "IC9") (pin "14") (pinfunction "CLK1_14") (pintype "input"))
      (node (ref "R68") (pin "2") (pinfunction "2_2") (pintype "passive"))
    )
    (net (code "24") (name "/DDS1_SYNC_IN_N") (class "Default")
      (node (ref "IC9") (pin "31") (pinfunction "~{Q1}_31") (pintype "output"))
    )
    (net (code "25") (name "/DDS1_SYNC_IN_P") (class "Default")
      (node (ref "IC9") (pin "32") (pinfunction "Q1_32") (pintype "output"))
    )
    (net (code "26") (name "/DDS2_SYNC_IN_N") (class "Default")
      (node (ref "IC9") (pin "25") (pinfunction "~{Q4}_25") (pintype "output"))
    )
    (net (code "27") (name "/DDS2_SYNC_IN_P") (class "Default")
      (node (ref "IC9") (pin "26") (pinfunction "Q4_26") (pintype "output"))
    )
    (net (code "28") (name "/DDS3_SYNC_IN_N") (class "Default")
      (node (ref "IC9") (pin "27") (pinfunction "~{Q3}_27") (pintype "output"))
    )
    (net (code "29") (name "/DDS3_SYNC_IN_P") (class "Default")
      (node (ref "IC9") (pin "28") (pinfunction "Q3_28") (pintype "output"))
    )
    (net (code "77") (name "/DDS_SYNC_CLK0") (class "Default")
      (node (ref "R31") (pin "2") (pinfunction "2_2") (pintype "passive"))
    )
    (net (code "78") (name "/DDS_SYNC_CLKSEL") (class "Default")
      (node (ref "IC9") (pin "8") (pinfunction "CLK_SEL_8") (pintype "input"))
    )
    (net (code "79") (name "/DDS_SYNC_CLK_OUTEN") (class "Default")
      (node (ref "IC4") (pin "3") (pinfunction "EN_3") (pintype "input"))
    )
    (net (code "80") (name "/DDS_SYNC_OUTEN") (class "Default")
      (node (ref "IC16") (pin "3") (pinfunction "EN_3") (pintype "input"))
      (node (ref "IC9") (pin "24") (pinfunction "OE5_24") (pintype "input"))
    )
    (net (code "86") (name "/FB_SYNC_N") (class "Default")
      (node (ref "IC16") (pin "1") (pinfunction "RIN-_1") (pintype "input"))
      (node (ref "IC9") (pin "20") (pinfunction "~{Q5}_20") (pintype "output"))
      (node (ref "R114") (pin "2") (pinfunction "2_2") (pintype "passive"))
    )
    (net (code "87") (name "/FB_SYNC_P") (class "Default")
      (node (ref "IC16") (pin "8") (pinfunction "RIN+_8") (pintype "input"))
      (node (ref "IC9") (pin "21") (pinfunction "Q5_21") (pintype "output"))
      (node (ref "R114") (pin "1") (pinfunction "1_1") (pintype "passive"))
    )
    (net (code "90") (name "/INT_CLK_IN") (class "Default")
      (node (ref "J7") (pin "1") (pinfunction "1_1") (pintype "bidirectional"))
    )
    (net (code "108") (name "/LED0") (class "Default")
      (node (ref "R27") (pin "1") (pinfunction "1_1") (pintype "passive"))
    )
    (net (code "109") (name "/LED1") (class "Default")
      (node (ref "R28") (pin "1") (pinfunction "1_1") (pintype "passive"))
    )
    (net (code "110") (name "/LED2") (class "Default")
      (node (ref "R29") (pin "1") (pinfunction "1_1") (pintype "passive"))
    )
    (net (code "111") (name "/LED3") (class "Default")
      (node (ref "R30") (pin "1") (pinfunction "1_1") (pintype "passive"))
    )
    (net (code "112") (name "/LED4") (class "Default")
      (node (ref "R43") (pin "1") (pinfunction "1_1") (pintype "passive"))
    )
    (net (code "113") (name "/LED5") (class "Default")
      (node (ref "R44") (pin "1") (pinfunction "1_1") (pintype "passive"))
    )
    (net (code "114") (name "/LED6") (class "Default")
      (node (ref "R25") (pin "1") (pinfunction "1_1") (pintype "passive"))
    )
    (net (code "115") (name "/LED7") (class "Default")
      (node (ref "R26") (pin "1") (pinfunction "1_1") (pintype "passive"))
    )
    (net (code "118") (name "/LVDS0_N_1") (class "Default")
      (node (ref "IC4") (pin "5") (pinfunction "DOUT-_5") (pintype "output"))
    )
    (net (code "120") (name "/LVDS0_P_1") (class "Default")
      (node (ref "IC4") (pin "6") (pinfunction "DOUT+_6") (pintype "output"))
    )
    (net (code "122") (name "/LVDS1_N_1") (class "Default")
      (node (ref "IC16") (pin "5") (pinfunction "DOUT-_5") (pintype "output"))
    )
    (net (code "124") (name "/LVDS1_P_1") (class "Default")
      (node (ref "IC16") (pin "6") (pinfunction "DOUT+_6") (pintype "output"))
    )
    (net (code "126") (name "/LVDS7_N_1") (class "Default")
      (node (ref "IC9") (pin "11") (pinfunction "~{CLK0}_11") (pintype "input"))
    )
    (net (code "128") (name "/LVDS7_P_1") (class "Default")
      (node (ref "IC9") (pin "10") (pinfunction "CLK0_10") (pintype "input"))
    )
    (net (code "134") (name "/RF_OUT0") (class "Default")
      (node (ref "J3") (pin "1") (pinfunction "1_1") (pintype "bidirectional"))
    )
    (net (code "135") (name "/RF_OUT1") (class "Default")
      (node (ref "J4") (pin "1") (pinfunction "1_1") (pintype "bidirectional"))
    )
    (net (code "136") (name "/RF_OUT2") (class "Default")
      (node (ref "J5") (pin "1") (pinfunction "1_1") (pintype "bidirectional"))
    )
    (net (code "137") (name "/RF_OUT3") (class "Default")
      (node (ref "J6") (pin "1") (pinfunction "1_1") (pintype "bidirectional"))
    )
    (net (code "140") (name "/SG0") (class "Default")
      (node (ref "C37") (pin "1") (pinfunction "1_1") (pintype "passive"))
      (node (ref "C42") (pin "2") (pinfunction "2_2") (pintype "passive"))
      (node (ref "J2") (pin "2") (pinfunction "2_2") (pintype "bidirectional"))
      (node (ref "R6") (pin "2") (pinfunction "2_2") (pintype "passive"))
    )
    (net (code "141") (name "/SG1") (class "Default")
      (node (ref "C11") (pin "1") (pinfunction "1_1") (pintype "passive"))
      (node (ref "C25") (pin "2") (pinfunction "2_2") (pintype "passive"))
      (node (ref "J3") (pin "2") (pinfunction "2_2") (pintype "bidirectional"))
      (node (ref "R64") (pin "2") (pinfunction "2_2") (pintype "passive"))
    )
    (net (code "142") (name "/SG2") (class "Default")
      (node (ref "C31") (pin "1") (pinfunction "1_1") (pintype "passive"))
      (node (ref "C32") (pin "2") (pinfunction "2_2") (pintype "passive"))
      (node (ref "J4") (pin "2") (pinfunction "2_2") (pintype "bidirectional"))
      (node (ref "R65") (pin "2") (pinfunction "2_2") (pintype "passive"))
    )
    (net (code "143") (name "/SG3") (class "Default")
      (node (ref "C33") (pin "1") (pinfunction "1_1") (pintype "passive"))
      (node (ref "C34") (pin "2") (pinfunction "2_2") (pintype "passive"))
      (node (ref "J5") (pin "2") (pinfunction "2_2") (pintype "bidirectional"))
      (node (ref "R74") (pin "2") (pinfunction "2_2") (pintype "passive"))
    )
    (net (code "144") (name "/SG4") (class "Default")
      (node (ref "C35") (pin "1") (pinfunction "1_1") (pintype "passive"))
      (node (ref "C41") (pin "2") (pinfunction "2_2") (pintype "passive"))
      (node (ref "J6") (pin "2") (pinfunction "2_2") (pintype "bidirectional"))
      (node (ref "R75") (pin "2") (pinfunction "2_2") (pintype "passive"))
    )
    (net (code "177") (name "GND") (class "Default")
      (node (ref "C1") (pin "1") (pinfunction "1_1") (pintype "passive"))
      (node (ref "C11") (pin "2") (pinfunction "2_2") (pintype "passive"))
      (node (ref "C13") (pin "1") (pinfunction "1_1") (pintype "passive"))
      (node (ref "C25") (pin "1") (pinfunction "1_1") (pintype "passive"))
      (node (ref "C31") (pin "2") (pinfunction "2_2") (pintype "passive"))
      (node (ref "C32") (pin "1") (pinfunction "1_1") (pintype "passive"))
      (node (ref "C33") (pin "2") (pinfunction "2_2") (pintype "passive"))
      (node (ref "C34") (pin "1") (pinfunction "1_1") (pintype "passive"))
      (node (ref "C35") (pin "2") (pinfunction "2_2") (pintype "passive"))
      (node (ref "C37") (pin "2") (pinfunction "2_2") (pintype "passive"))
      (node (ref "C41") (pin "1") (pinfunction "1_1") (pintype "passive"))
      (node (ref "C42") (pin "1") (pinfunction "1_1") (pintype "passive"))
      (node (ref "C45") (pin "1") (pinfunction "1_1") (pintype "passive"))
      (node (ref "C46") (pin "1") (pinfunction "1_1") (pintype "passive"))
      (node (ref "C86") (pin "1") (pinfunction "1_1") (pintype "passive"))
      (node (ref "C89") (pin "1") (pinfunction "1_1") (pintype "passive"))
      (node (ref "C90") (pin "1") (pinfunction "1_1") (pintype "passive"))
      (node (ref "CLIP1") (pin "1") (pinfunction "1_1") (pintype "passive"))
      (node (ref "CLIP10") (pin "1") (pinfunction "1_1") (pintype "passive"))
      (node (ref "CLIP11") (pin "1") (pinfunction "1_1") (pintype "passive"))
      (node (ref "CLIP12") (pin "1") (pinfunction "1_1") (pintype "passive"))
      (node (ref "CLIP13") (pin "1") (pinfunction "1_1") (pintype "passive"))
      (node (ref "CLIP14") (pin "1") (pinfunction "1_1") (pintype "passive"))
      (node (ref "CLIP15") (pin "1") (pinfunction "1_1") (pintype "passive"))
      (node (ref "CLIP16") (pin "1") (pinfunction "1_1") (pintype "passive"))
      (node (ref "CLIP17") (pin "1") (pinfunction "1_1") (pintype "passive"))
      (node (ref "CLIP18") (pin "1") (pinfunction "1_1") (pintype "passive"))
      (node (ref "CLIP19") (pin "1") (pinfunction "1_1") (pintype "passive"))
      (node (ref "CLIP2") (pin "1") (pinfunction "1_1") (pintype "passive"))
      (node (ref "CLIP20") (pin "1") (pinfunction "1_1") (pintype "passive"))
      (node (ref "CLIP21") (pin "1") (pinfunction "1_1") (pintype "passive"))
      (node (ref "CLIP22") (pin "1") (pinfunction "1_1") (pintype "passive"))
      (node (ref "CLIP23") (pin "1") (pinfunction "1_1") (pintype "passive"))
      (node (ref "CLIP24") (pin "1") (pinfunction "1_1") (pintype "passive"))
      (node (ref "CLIP25") (pin "1") (pinfunction "1_1") (pintype "passive"))
      (node (ref "CLIP26") (pin "1") (pinfunction "1_1") (pintype "passive"))
      (node (ref "CLIP27") (pin "1") (pinfunction "1_1") (pintype "passive"))
      (node (ref "CLIP28") (pin "1") (pinfunction "1_1") (pintype "passive"))
      (node (ref "CLIP29") (pin "1") (pinfunction "1_1") (pintype "passive"))
      (node (ref "CLIP3") (pin "1") (pinfunction "1_1") (pintype "passive"))
      (node (ref "CLIP30") (pin "1") (pinfunction "1_1") (pintype "passive"))
      (node (ref "CLIP31") (pin "1") (pinfunction "1_1") (pintype "passive"))
      (node (ref "CLIP4") (pin "1") (pinfunction "1_1") (pintype "passive"))
      (node (ref "CLIP5") (pin "1") (pinfunction "1_1") (pintype "passive"))
      (node (ref "CLIP6") (pin "1") (pinfunction "1_1") (pintype "passive"))
      (node (ref "CLIP7") (pin "1") (pinfunction "1_1") (pintype "passive"))
      (node (ref "CLIP8") (pin "1") (pinfunction "1_1") (pintype "passive"))
      (node (ref "CLIP9") (pin "1") (pinfunction "1_1") (pintype "passive"))
      (node (ref "IC16") (pin "2") (pinfunction "GND_2") (pintype "power_in"))
      (node (ref "IC16") (pin "4") (pinfunction "GND_4") (pintype "output"))
      (node (ref "IC4") (pin "2") (pinfunction "GND_2") (pintype "power_in"))
      (node (ref "IC4") (pin "4") (pinfunction "GND_4") (pintype "output"))
      (node (ref "IC9") (pin "12") (pinfunction "OE2_12") (pintype "input"))
      (node (ref "IC9") (pin "2") (pinfunction "SFOUTA1_2") (pintype "input"))
      (node (ref "IC9") (pin "22") (pinfunction "SFOUTB0_22") (pintype "input"))
      (node (ref "IC9") (pin "23") (pinfunction "SFOUTB1_23") (pintype "input"))
      (node (ref "IC9") (pin "3") (pinfunction "SFOUTA0_3") (pintype "input"))
      (node (ref "IC9") (pin "33") (pinfunction "GND_33") (pintype "power_in"))
      (node (ref "IC9") (pin "6") (pinfunction "GND_6") (pintype "power_in"))
      (node (ref "J7") (pin "2") (pinfunction "2_2") (pintype "bidirectional"))
      (node (ref "LD2") (pin "1") (pinfunction "C_1") (pintype "passive"))
      (node (ref "LD2") (pin "3") (pinfunction "C_3") (pintype "passive"))
      (node (ref "LD5") (pin "1") (pinfunction "C_1") (pintype "passive"))
      (node (ref "LD5") (pin "3") (pinfunction "C_3") (pintype "passive"))
      (node (ref "LD6") (pin "1") (pinfunction "C_1") (pintype "passive"))
      (node (ref "LD6") (pin "3") (pinfunction "C_3") (pintype "passive"))
      (node (ref "LD8") (pin "1") (pinfunction "C_1") (pintype "passive"))
      (node (ref "LD8") (pin "3") (pinfunction "C_3") (pintype "passive"))
      (node (ref "R39") (pin "1") (pinfunction "1_1") (pintype "passive"))
      (node (ref "R6") (pin "1") (pinfunction "1_1") (pintype "passive"))
      (node (ref "R64") (pin "1") (pinfunction "1_1") (pintype "passive"))
      (node (ref "R65") (pin "1") (pinfunction "1_1") (pintype "passive"))
      (node (ref "R74") (pin "1") (pinfunction "1_1") (pintype "passive"))
      (node (ref "R75") (pin "1") (pinfunction "1_1") (pintype "passive"))
    )
    (net (code "178") (name "Net-(IC4-RIN+)") (class "Default")
      (node (ref "IC4") (pin "8") (pinfunction "RIN+_8") (pintype "input"))
      (node (ref "R31") (pin "1") (pinfunction "1_1") (pintype "passive"))
      (node (ref "R32") (pin "2") (pinfunction "2_2") (pintype "passive"))
    )
    (net (code "179") (name "Net-(IC4-RIN-)") (class "Default")
      (node (ref "C1") (pin "2") (pinfunction "2_2") (pintype "passive"))
      (node (ref "IC4") (pin "1") (pinfunction "RIN-_1") (pintype "input"))
      (node (ref "R32") (pin "1") (pinfunction "1_1") (pintype "passive"))
      (node (ref "R36") (pin "1") (pinfunction "1_1") (pintype "passive"))
      (node (ref "R39") (pin "2") (pinfunction "2_2") (pintype "passive"))
    )
    (net (code "180") (name "Net-(LD2A-A)") (class "Default")
      (node (ref "LD2") (pin "2") (pinfunction "A_2") (pintype "passive"))
      (node (ref "R25") (pin "2") (pinfunction "2_2") (pintype "passive"))
    )
    (net (code "181") (name "Net-(LD2B-A)") (class "Default")
      (node (ref "LD2") (pin "4") (pinfunction "A_4") (pintype "passive"))
      (node (ref "R26") (pin "2") (pinfunction "2_2") (pintype "passive"))
    )
    (net (code "182") (name "Net-(LD5A-A)") (class "Default")
      (node (ref "LD5") (pin "2") (pinfunction "A_2") (pintype "passive"))
      (node (ref "R27") (pin "2") (pinfunction "2_2") (pintype "passive"))
    )
    (net (code "183") (name "Net-(LD5B-A)") (class "Default")
      (node (ref "LD5") (pin "4") (pinfunction "A_4") (pintype "passive"))
      (node (ref "R28") (pin "2") (pinfunction "2_2") (pintype "passive"))
    )
    (net (code "184") (name "Net-(LD6A-A)") (class "Default")
      (node (ref "LD6") (pin "2") (pinfunction "A_2") (pintype "passive"))
      (node (ref "R29") (pin "2") (pinfunction "2_2") (pintype "passive"))
    )
    (net (code "185") (name "Net-(LD6B-A)") (class "Default")
      (node (ref "LD6") (pin "4") (pinfunction "A_4") (pintype "passive"))
      (node (ref "R30") (pin "2") (pinfunction "2_2") (pintype "passive"))
    )
    (net (code "186") (name "Net-(LD8A-A)") (class "Default")
      (node (ref "LD8") (pin "2") (pinfunction "A_2") (pintype "passive"))
      (node (ref "R43") (pin "2") (pinfunction "2_2") (pintype "passive"))
    )
    (net (code "187") (name "Net-(LD8B-A)") (class "Default")
      (node (ref "LD8") (pin "4") (pinfunction "A_4") (pintype "passive"))
      (node (ref "R44") (pin "2") (pinfunction "2_2") (pintype "passive"))
    )
    (net (code "188") (name "P3V3") (class "Default")
      (node (ref "L13") (pin "2") (pinfunction "2_2") (pintype "passive"))
      (node (ref "L8") (pin "2") (pinfunction "2_2") (pintype "passive"))
    )
    (net (code "189") (name "P3V3_CLK1") (class "Default")
      (node (ref "C86") (pin "2") (pinfunction "2_2") (pintype "passive"))
      (node (ref "C89") (pin "2") (pinfunction "2_2") (pintype "passive"))
      (node (ref "C90") (pin "2") (pinfunction "2_2") (pintype "passive"))
      (node (ref "IC9") (pin "1") (pinfunction "OE0_1") (pintype "input"))
      (node (ref "IC9") (pin "13") (pinfunction "OE3_13") (pintype "input"))
      (node (ref "IC9") (pin "16") (pinfunction "OE4_16") (pintype "input"))
      (node (ref "IC9") (pin "18") (pinfunction "VDDOA_18") (pintype "power_in"))
      (node (ref "IC9") (pin "19") (pinfunction "VDDOB_19") (pintype "power_in"))
      (node (ref "IC9") (pin "7") (pinfunction "VDD_7") (pintype "power_in"))
      (node (ref "IC9") (pin "9") (pinfunction "OE1_9") (pintype "input"))
      (node (ref "L13") (pin "1") (pinfunction "1_1") (pintype "passive"))
    )
    (net (code "190") (name "P3V3_CLK2") (class "Default")
      (node (ref "C13") (pin "2") (pinfunction "2_2") (pintype "passive"))
      (node (ref "C45") (pin "2") (pinfunction "2_2") (pintype "passive"))
      (node (ref "C46") (pin "2") (pinfunction "2_2") (pintype "passive"))
      (node (ref "IC16") (pin "7") (pinfunction "VCC_7") (pintype "power_in"))
      (node (ref "IC4") (pin "7") (pinfunction "VCC_7") (pintype "power_in"))
      (node (ref "L8") (pin "1") (pinfunction "1_1") (pintype "passive"))
      (node (ref "R36") (pin "2") (pinfunction "2_2") (pintype "passive"))
    )
    (net (code "191") (name "unconnected-(IC9-Q2-Pad30)") (class "Default")
      (node (ref "IC9") (pin "30") (pinfunction "Q2_30") (pintype "output"))
    )
    (net (code "192") (name "unconnected-(IC9-VREF-Pad17)") (class "Default")
      (node (ref "IC9") (pin "17") (pinfunction "VREF_17") (pintype "output"))
    )
    (net (code "193") (name "unconnected-(IC9-~{Q2}-Pad29)") (class "Default")
      (node (ref "IC9") (pin "29") (pinfunction "~{Q2}_29") (pintype "output"))
    )
  )
)
